# ATX_Power_Breakout_v1p1.net
KiCad netlist of a schematic drawn in EAGLE
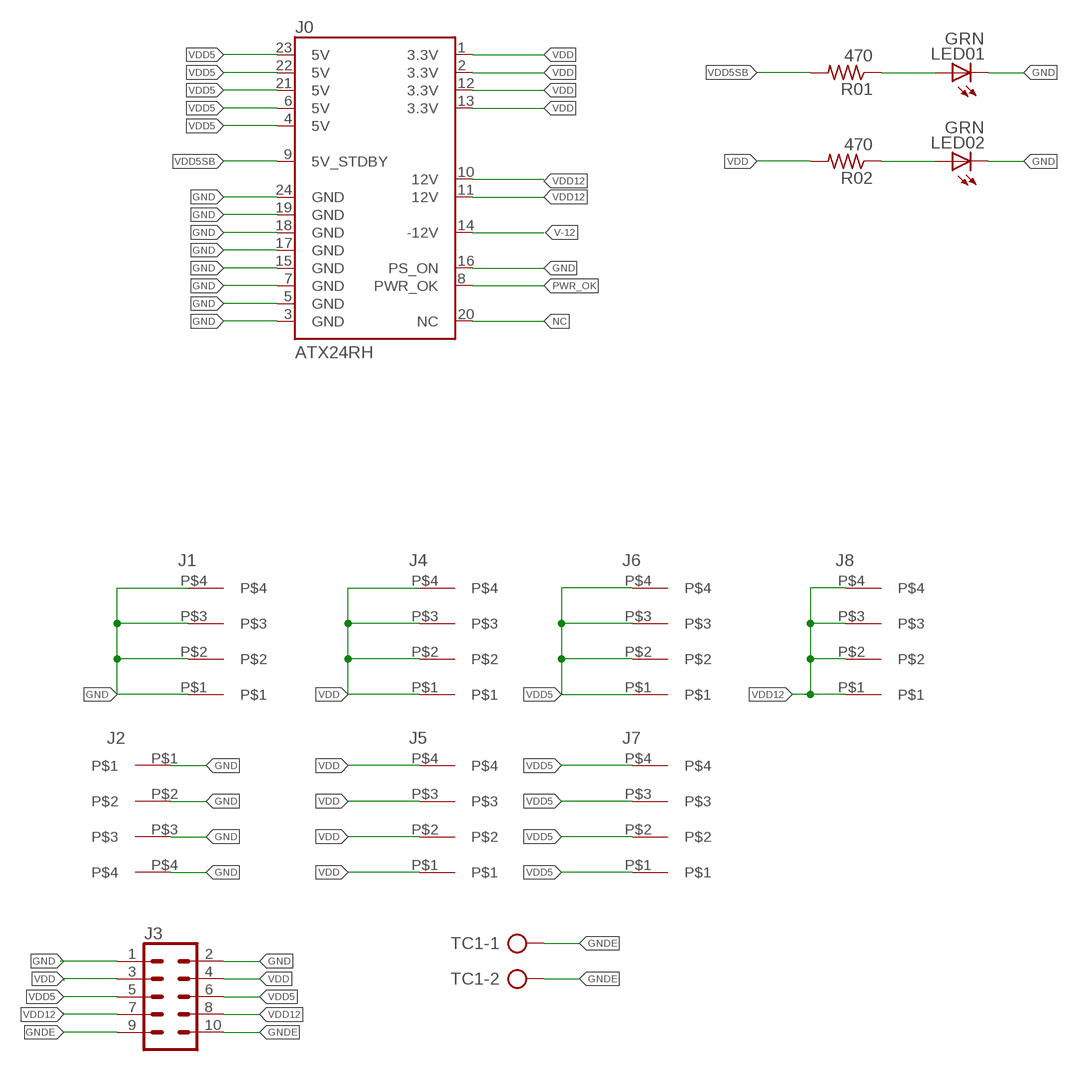
[diagram p0: schematic, sheet 1]

(export (version "E")
  (design (tool "Eeschema 10.0.6"))
  (components
    (comp (ref "J0")
      (value "ATX24RH")
      (footprint "eagle-import:ATX24_RIGHT_ANGLE")
      (libsource (lib "eagle-import") (part "ATX24RH"))
    )
    (comp (ref "J1")
      (value "3.81MM_1_X_4_RT_ANGLE_PLUG_HEADER")
      (footprint "eagle-import:1X4_3.81MM_PITCH")
      (libsource (lib "eagle-import") (part "3.81MM_1_X_4_RT_ANGLE_PLUG_HEADER"))
    )
    (comp (ref "J2")
      (value "3.81MM_1_X_4_RT_ANGLE_PLUG_HEADER")
      (footprint "eagle-import:1X4_3.81MM_PITCH")
      (libsource (lib "eagle-import") (part "3.81MM_1_X_4_RT_ANGLE_PLUG_HEADER"))
    )
    (comp (ref "J3")
      (value "CONN_05X2PTH")
      (footprint "eagle-import:2X5")
      (libsource (lib "eagle-import") (part "CONN_05X2PTH"))
    )
    (comp (ref "J4")
      (value "3.81MM_1_X_4_RT_ANGLE_PLUG_HEADER")
      (footprint "eagle-import:1X4_3.81MM_PITCH")
      (libsource (lib "eagle-import") (part "3.81MM_1_X_4_RT_ANGLE_PLUG_HEADER"))
    )
    (comp (ref "J5")
      (value "3.81MM_1_X_4_RT_ANGLE_PLUG_HEADER")
      (footprint "eagle-import:1X4_3.81MM_PITCH")
      (libsource (lib "eagle-import") (part "3.81MM_1_X_4_RT_ANGLE_PLUG_HEADER"))
    )
    (comp (ref "J6")
      (value "3.81MM_1_X_4_RT_ANGLE_PLUG_HEADER")
      (footprint "eagle-import:1X4_3.81MM_PITCH")
      (libsource (lib "eagle-import") (part "3.81MM_1_X_4_RT_ANGLE_PLUG_HEADER"))
    )
    (comp (ref "J7")
      (value "3.81MM_1_X_4_RT_ANGLE_PLUG_HEADER")
      (footprint "eagle-import:1X4_3.81MM_PITCH")
      (libsource (lib "eagle-import") (part "3.81MM_1_X_4_RT_ANGLE_PLUG_HEADER"))
    )
    (comp (ref "J8")
      (value "3.81MM_1_X_4_RT_ANGLE_PLUG_HEADER")
      (footprint "eagle-import:1X4_3.81MM_PITCH")
      (libsource (lib "eagle-import") (part "3.81MM_1_X_4_RT_ANGLE_PLUG_HEADER"))
    )
    (comp (ref "LED01")
      (value "GREEN")
      (footprint "eagle-import:LED_0805_GREEN")
      (libsource (lib "eagle-import") (part "LED_0805_GREEN"))
    )
    (comp (ref "LED02")
      (value "GREEN")
      (footprint "eagle-import:LED_0805_GREEN")
      (libsource (lib "eagle-import") (part "LED_0805_GREEN"))
    )
    (comp (ref "R01")
      (value "470")
      (footprint "eagle-import:0402")
      (libsource (lib "eagle-import") (part "R_0402"))
    )
    (comp (ref "R02")
      (value "470")
      (footprint "eagle-import:0402")
      (libsource (lib "eagle-import") (part "R_0402"))
    )
    (comp (ref "TC1")
      (value "AK300/2")
      (footprint "eagle-import:AK300_2")
      (libsource (lib "eagle-import") (part "AK300/2"))
    )
  )
  (nets
    (net (code "1") (name "GND") (class "Default")
      (node (ref "J0") (pin "15") (pinfunction "GND_15") (pintype "bidirectional"))
      (node (ref "J0") (pin "16") (pinfunction "PS_ON_16") (pintype "bidirectional"))
      (node (ref "J0") (pin "17") (pinfunction "GND_17") (pintype "bidirectional"))
      (node (ref "J0") (pin "18") (pinfunction "GND_18") (pintype "bidirectional"))
      (node (ref "J0") (pin "19") (pinfunction "GND_19") (pintype "bidirectional"))
      (node (ref "J0") (pin "24") (pinfunction "GND_24") (pintype "bidirectional"))
      (node (ref "J0") (pin "3") (pinfunction "GND_3") (pintype "bidirectional"))
      (node (ref "J0") (pin "5") (pinfunction "GND_5") (pintype "bidirectional"))
      (node (ref "J0") (pin "7") (pinfunction "GND_7") (pintype "bidirectional"))
      (node (ref "J1") (pin "P$1") (pinfunction "P$1_P$1") (pintype "bidirectional"))
      (node (ref "J1") (pin "P$2") (pinfunction "P$2_P$2") (pintype "bidirectional"))
      (node (ref "J1") (pin "P$3") (pinfunction "P$3_P$3") (pintype "bidirectional"))
      (node (ref "J1") (pin "P$4") (pinfunction "P$4_P$4") (pintype "bidirectional"))
      (node (ref "J2") (pin "P$1") (pinfunction "P$1_P$1") (pintype "bidirectional"))
      (node (ref "J2") (pin "P$2") (pinfunction "P$2_P$2") (pintype "bidirectional"))
      (node (ref "J2") (pin "P$3") (pinfunction "P$3_P$3") (pintype "bidirectional"))
      (node (ref "J2") (pin "P$4") (pinfunction "P$4_P$4") (pintype "bidirectional"))
      (node (ref "J3") (pin "1") (pinfunction "1_1") (pintype "passive"))
      (node (ref "J3") (pin "2") (pinfunction "2_2") (pintype "passive"))
      (node (ref "LED01") (pin "C") (pinfunction "C_C") (pintype "passive"))
      (node (ref "LED02") (pin "C") (pinfunction "C_C") (pintype "passive"))
    )
    (net (code "2") (name "GNDE") (class "Default")
      (node (ref "J3") (pin "10") (pinfunction "10_10") (pintype "passive"))
      (node (ref "J3") (pin "9") (pinfunction "9_9") (pintype "passive"))
      (node (ref "TC1") (pin "1") (pinfunction "KL_1") (pintype "passive"))
      (node (ref "TC1") (pin "2") (pinfunction "KL_2") (pintype "passive"))
    )
    (net (code "3") (name "NC") (class "Default")
      (node (ref "J0") (pin "20") (pinfunction "NC_20") (pintype "bidirectional"))
    )
    (net (code "4") (name "Net-(R01-1)") (class "Default")
      (node (ref "LED01") (pin "A") (pinfunction "A_A") (pintype "passive"))
      (node (ref "R01") (pin "P$1") (pinfunction "1_P$1") (pintype "passive"))
    )
    (net (code "5") (name "Net-(R02-1)") (class "Default")
      (node (ref "LED02") (pin "A") (pinfunction "A_A") (pintype "passive"))
      (node (ref "R02") (pin "P$1") (pinfunction "1_P$1") (pintype "passive"))
    )
    (net (code "6") (name "PWR_OK") (class "Default")
      (node (ref "J0") (pin "8") (pinfunction "PWR_OK_8") (pintype "bidirectional"))
    )
    (net (code "7") (name "V-12") (class "Default")
      (node (ref "J0") (pin "14") (pinfunction "-12V_14") (pintype "bidirectional"))
    )
    (net (code "8") (name "VDD") (class "Default")
      (node (ref "J0") (pin "1") (pinfunction "3.3V_1") (pintype "bidirectional"))
      (node (ref "J0") (pin "12") (pinfunction "3.3V_12") (pintype "bidirectional"))
      (node (ref "J0") (pin "13") (pinfunction "3.3V_13") (pintype "bidirectional"))
      (node (ref "J0") (pin "2") (pinfunction "3.3V_2") (pintype "bidirectional"))
      (node (ref "J3") (pin "3") (pinfunction "3_3") (pintype "passive"))
      (node (ref "J3") (pin "4") (pinfunction "4_4") (pintype "passive"))
      (node (ref "J4") (pin "P$1") (pinfunction "P$1_P$1") (pintype "bidirectional"))
      (node (ref "J4") (pin "P$2") (pinfunction "P$2_P$2") (pintype "bidirectional"))
      (node (ref "J4") (pin "P$3") (pinfunction "P$3_P$3") (pintype "bidirectional"))
      (node (ref "J4") (pin "P$4") (pinfunction "P$4_P$4") (pintype "bidirectional"))
      (node (ref "J5") (pin "P$1") (pinfunction "P$1_P$1") (pintype "bidirectional"))
      (node (ref "J5") (pin "P$2") (pinfunction "P$2_P$2") (pintype "bidirectional"))
      (node (ref "J5") (pin "P$3") (pinfunction "P$3_P$3") (pintype "bidirectional"))
      (node (ref "J5") (pin "P$4") (pinfunction "P$4_P$4") (pintype "bidirectional"))
      (node (ref "R02") (pin "P$2") (pinfunction "2_P$2") (pintype "passive"))
    )
    (net (code "9") (name "VDD5") (class "Default")
      (node (ref "J0") (pin "21") (pinfunction "5V_21") (pintype "bidirectional"))
      (node (ref "J0") (pin "22") (pinfunction "5V_22") (pintype "bidirectional"))
      (node (ref "J0") (pin "23") (pinfunction "5V_23") (pintype "bidirectional"))
      (node (ref "J0") (pin "4") (pinfunction "5V_4") (pintype "bidirectional"))
      (node (ref "J0") (pin "6") (pinfunction "5V_6") (pintype "bidirectional"))
      (node (ref "J3") (pin "5") (pinfunction "5_5") (pintype "passive"))
      (node (ref "J3") (pin "6") (pinfunction "6_6") (pintype "passive"))
      (node (ref "J6") (pin "P$1") (pinfunction "P$1_P$1") (pintype "bidirectional"))
      (node (ref "J6") (pin "P$2") (pinfunction "P$2_P$2") (pintype "bidirectional"))
      (node (ref "J6") (pin "P$3") (pinfunction "P$3_P$3") (pintype "bidirectional"))
      (node (ref "J6") (pin "P$4") (pinfunction "P$4_P$4") (pintype "bidirectional"))
      (node (ref "J7") (pin "P$1") (pinfunction "P$1_P$1") (pintype "bidirectional"))
      (node (ref "J7") (pin "P$2") (pinfunction "P$2_P$2") (pintype "bidirectional"))
      (node (ref "J7") (pin "P$3") (pinfunction "P$3_P$3") (pintype "bidirectional"))
      (node (ref "J7") (pin "P$4") (pinfunction "P$4_P$4") (pintype "bidirectional"))
    )
    (net (code "10") (name "VDD5SB") (class "Default")
      (node (ref "J0") (pin "9") (pinfunction "5V_STDBY_9") (pintype "bidirectional"))
      (node (ref "R01") (pin "P$2") (pinfunction "2_P$2") (pintype "passive"))
    )
    (net (code "11") (name "VDD12") (class "Default")
      (node (ref "J0") (pin "10") (pinfunction "12V_10") (pintype "bidirectional"))
      (node (ref "J0") (pin "11") (pinfunction "12V_11") (pintype "bidirectional"))
      (node (ref "J3") (pin "7") (pinfunction "7_7") (pintype "passive"))
      (node (ref "J3") (pin "8") (pinfunction "8_8") (pintype "passive"))
      (node (ref "J8") (pin "P$1") (pinfunction "P$1_P$1") (pintype "bidirectional"))
      (node (ref "J8") (pin "P$2") (pinfunction "P$2_P$2") (pintype "bidirectional"))
      (node (ref "J8") (pin "P$3") (pinfunction "P$3_P$3") (pintype "bidirectional"))
      (node (ref "J8") (pin "P$4") (pinfunction "P$4_P$4") (pintype "bidirectional"))
    )
  )
)
